# 1Sheet1-IR-Sensor.net
KiCad netlist of a schematic drawn in Altium Designer
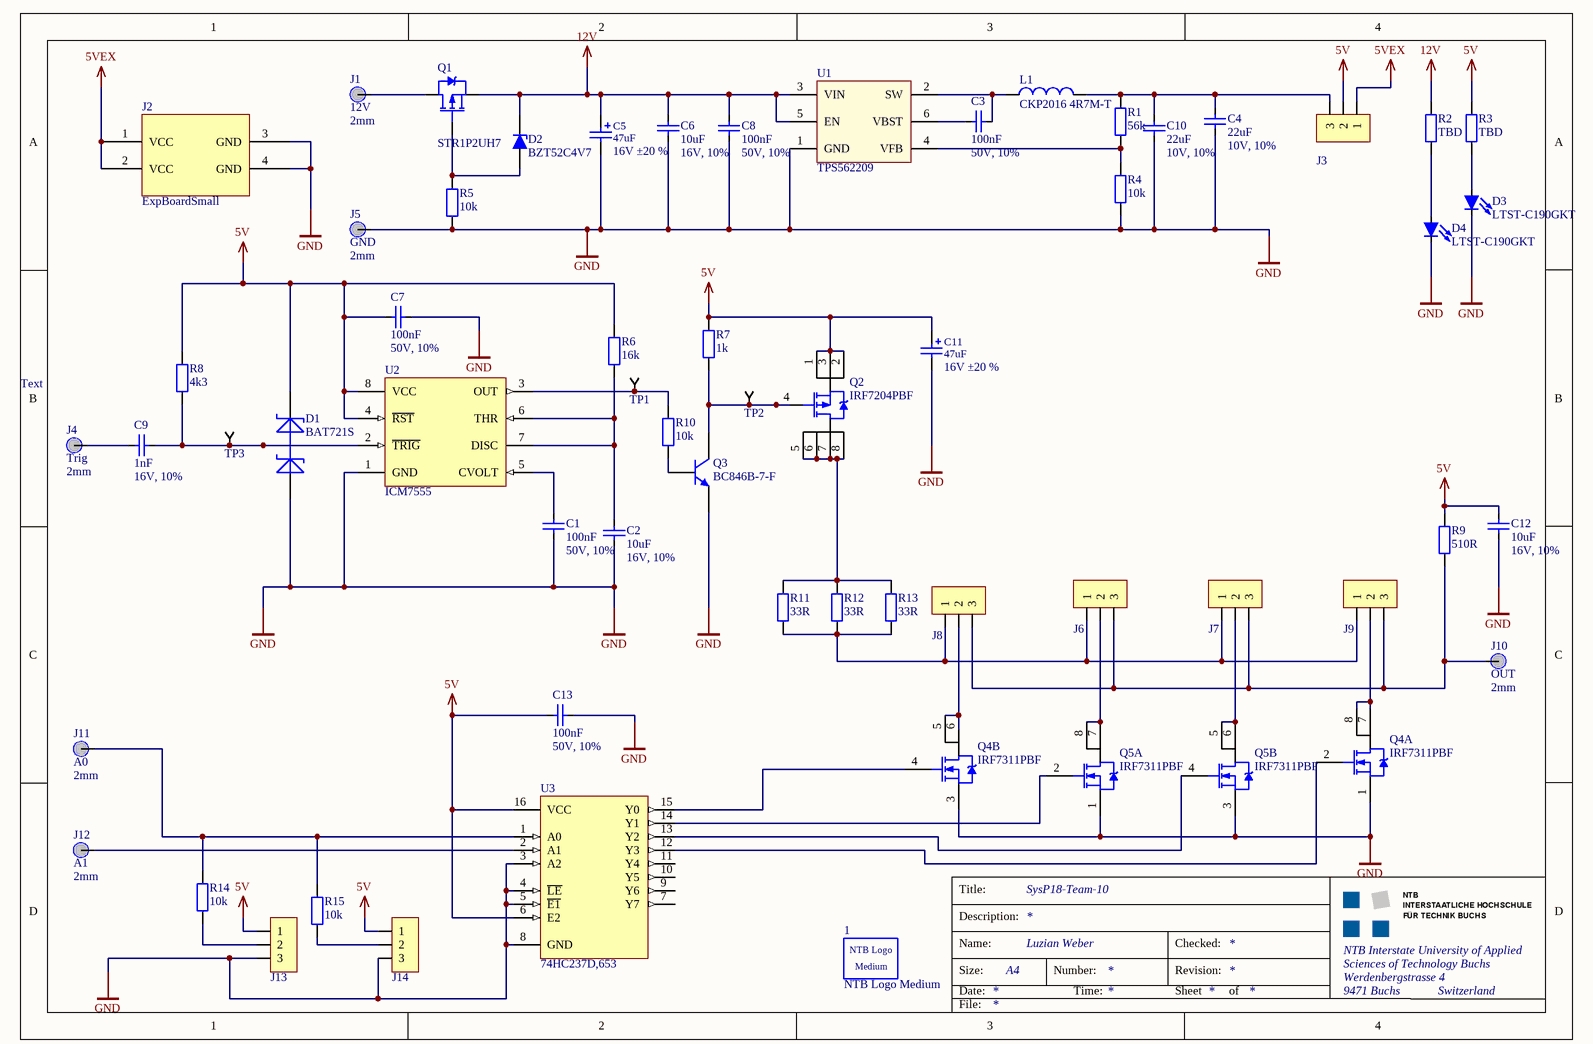
[diagram p0: 1Sheet1-IR-Sensor.SchDoc]

(export (version "E")
  (design (tool "Eeschema 10.0.6"))
  (components
    (comp (ref "1")
      (value "NTB Logo Medium")
      (footprint "NTB Logo Medium Copper")
      (libsource (lib "IR-Sensor") (part "NTB Logo Medium Copper"))
    )
    (comp (ref "C1")
      (value "100nF")
      (footprint "CAP-0805[2012]")
      (description "100n 50V X7R MLCC 0805 (1608 Metric)")
      (fields (field (name "TOLERANCE") "10%") (field (name "VALADDON") "50V, 10%"))
      (libsource (lib "IR-Sensor") (part "MLCC 0805 100n 50V"))
    )
    (comp (ref "C2")
      (value "10uF")
      (footprint "CAP-1206[3216]")
      (description "10u 16V X7R MLCC 1206 (3016 Metric)")
      (fields (field (name "TOLERANCE") "10%") (field (name "VALADDON") "16V, 10%"))
      (libsource (lib "IR-Sensor") (part "MLCC 1206 10u 16V"))
    )
    (comp (ref "C3")
      (value "100nF")
      (footprint "CAP-0805[2012]")
      (description "100n 50V X7R MLCC 0805 (1608 Metric)")
      (fields (field (name "TOLERANCE") "10%") (field (name "VALADDON") "50V, 10%"))
      (libsource (lib "IR-Sensor") (part "MLCC 0805 100n 50V"))
    )
    (comp (ref "C4")
      (value "22uF")
      (footprint "CAP-1206[3216]")
      (description "22u 10V X7R MLCC 1206 (3016 Metric)")
      (fields (field (name "TOLERANCE") "10%") (field (name "VALADDON") "10V, 10%"))
      (libsource (lib "IR-Sensor") (part "MLCC 1206 22u 10V"))
    )
    (comp (ref "C5")
      (value "47uF")
      (footprint "CDE_CAP AVE CODE D_H")
      (description "ELKO, 47uF, 16V, CDE_AVE476M16D16T-F_AVE CODE D")
      (fields
        (field (name "MANUFACTURER") "Cornell Dubilier")
        (field (name "VALUEADDON") "16V ±20 %")
        (field (name "Comment") "AVE476M16D16T-F")
        (field (name "PUBLISHER") "Stefan Ursella, M.Eng")
      )
      (libsource (lib "IR-Sensor") (part "ELKO 47uF 16V"))
    )
    (comp (ref "C6")
      (value "10uF")
      (footprint "CAP-1206[3216]")
      (description "10u 16V X7R MLCC 1206 (3016 Metric)")
      (fields (field (name "TOLERANCE") "10%") (field (name "VALADDON") "16V, 10%"))
      (libsource (lib "IR-Sensor") (part "MLCC 1206 10u 16V"))
    )
    (comp (ref "C7")
      (value "100nF")
      (footprint "CAP-0805[2012]")
      (description "100n 50V X7R MLCC 0805 (1608 Metric)")
      (fields (field (name "TOLERANCE") "10%") (field (name "VALADDON") "50V, 10%"))
      (libsource (lib "IR-Sensor") (part "MLCC 0805 100n 50V"))
    )
    (comp (ref "C8")
      (value "100nF")
      (footprint "CAP-0805[2012]")
      (description "100n 50V X7R MLCC 0805 (1608 Metric)")
      (fields (field (name "TOLERANCE") "10%") (field (name "VALADDON") "50V, 10%"))
      (libsource (lib "IR-Sensor") (part "MLCC 0805 100n 50V"))
    )
    (comp (ref "C9")
      (value "1nF")
      (footprint "CAP-0805[2012]")
      (description "MLCC - SMD/SMT 0805 1000pF 16V C0G 10%")
      (fields
        (field (name "MANUFACTURER") "Vishay")
        (field (name "VALUEADDON") "16V, 10%")
        (field (name "PUBLISHER") "SCLM")
      )
      (libsource (lib "IR-Sensor") (part "MLCC 0805 1n 16V"))
    )
    (comp (ref "C10")
      (value "22uF")
      (footprint "CAP-1206[3216]")
      (description "22u 10V X7R MLCC 1206 (3016 Metric)")
      (fields (field (name "TOLERANCE") "10%") (field (name "VALADDON") "10V, 10%"))
      (libsource (lib "IR-Sensor") (part "MLCC 1206 22u 10V"))
    )
    (comp (ref "C11")
      (value "47uF")
      (footprint "CDE_CAP AVE CODE D_H")
      (description "ELKO, 47uF, 16V, CDE_AVE476M16D16T-F_AVE CODE D")
      (fields
        (field (name "MANUFACTURER") "Cornell Dubilier")
        (field (name "VALUEADDON") "16V ±20 %")
        (field (name "Comment") "AVE476M16D16T-F")
        (field (name "PUBLISHER") "Stefan Ursella, M.Eng")
      )
      (libsource (lib "IR-Sensor") (part "ELKO 47uF 16V"))
    )
    (comp (ref "C12")
      (value "10uF")
      (footprint "CAP-1206[3216]")
      (description "10u 16V X7R MLCC 1206 (3016 Metric)")
      (fields (field (name "TOLERANCE") "10%") (field (name "VALADDON") "16V, 10%"))
      (libsource (lib "IR-Sensor") (part "MLCC 1206 10u 16V"))
    )
    (comp (ref "C13")
      (value "100nF")
      (footprint "CAP-0805[2012]")
      (description "100n 50V X7R MLCC 0805 (1608 Metric)")
      (fields (field (name "TOLERANCE") "10%") (field (name "VALADDON") "50V, 10%"))
      (libsource (lib "IR-Sensor") (part "MLCC 0805 100n 50V"))
    )
    (comp (ref "D1")
      (value "BAT721S")
      (footprint "SOT-23")
      (description "NXP  BAT721S  SCHOTTKY-DIODE, 2FACH")
      (fields (field (name "MANUFACTURER") "NXP") (field (name "PUBLISHER") "SCNP"))
      (libsource (lib "IR-Sensor") (part "BAT721S-SOT23"))
    )
    (comp (ref "D2")
      (value "BZT52C4V7")
      (footprint "SOD-123")
      (description "4.7V Zener-Diode, BZT52C4V7")
      (libsource (lib "IR-Sensor") (part "BZT52C4V7"))
    )
    (comp (ref "D3")
      (value "LTST-C190GKT")
      (footprint "LED 0603 green")
      (description "LED SMD 0603 green 6mcd")
      (libsource (lib "IR-Sensor") (part "LED Green"))
    )
    (comp (ref "D4")
      (value "LTST-C190GKT")
      (footprint "LED 0603 green")
      (description "LED SMD 0603 green 6mcd")
      (libsource (lib "IR-Sensor") (part "LED Green"))
    )
    (comp (ref "J1")
      (value "12V")
      (footprint "Laborbuchse 2mm")
      (description "Laborbuchse")
      (fields (field (name "SIZE") "2mm") (field (name "PUBLISHER") "B.Sc. Ursella"))
      (libsource (lib "") (part "Laborbuchse_1"))
    )
    (comp (ref "J2")
      (value "ExpBoardSmall")
      (footprint "EXPBOARDCON")
      (libsource (lib "IR-Sensor") (part "ExpBoardSmall"))
    )
    (comp (ref "J3")
      (value "3 Pin Header")
      (footprint "3PIN HEADER 2.54MM")
      (description "3 Pin Header 2.54mm")
      (fields (field (name "PUBLISHER") "SCLM"))
      (libsource (lib "") (part "3 Pin Header_1"))
    )
    (comp (ref "J4")
      (value "Trig")
      (footprint "Laborbuchse 2mm")
      (description "Laborbuchse")
      (fields (field (name "SIZE") "2mm") (field (name "PUBLISHER") "B.Sc. Ursella"))
      (libsource (lib "") (part "Laborbuchse_1"))
    )
    (comp (ref "J5")
      (value "GND")
      (footprint "Laborbuchse 2mm")
      (description "Laborbuchse")
      (fields (field (name "SIZE") "2mm") (field (name "PUBLISHER") "B.Sc. Ursella"))
      (libsource (lib "") (part "Laborbuchse_1"))
    )
    (comp (ref "J6")
      (value "3 Pin Header Buchse")
      (footprint "3PIN HEADER SOCKET 2.54MM")
      (description "3 Pin Header 2.54mm Buchse")
      (libsource (lib "IR-Sensor") (part "3 Pin Header Buchse"))
    )
    (comp (ref "J7")
      (value "3 Pin Header Buchse")
      (footprint "3PIN HEADER SOCKET 2.54MM")
      (description "3 Pin Header 2.54mm Buchse")
      (libsource (lib "IR-Sensor") (part "3 Pin Header Buchse"))
    )
    (comp (ref "J8")
      (value "3 Pin Header Buchse")
      (footprint "3PIN HEADER SOCKET 2.54MM")
      (description "3 Pin Header 2.54mm Buchse")
      (libsource (lib "IR-Sensor") (part "3 Pin Header Buchse"))
    )
    (comp (ref "J9")
      (value "3 Pin Header Buchse")
      (footprint "3PIN HEADER SOCKET 2.54MM")
      (description "3 Pin Header 2.54mm Buchse")
      (libsource (lib "IR-Sensor") (part "3 Pin Header Buchse"))
    )
    (comp (ref "J10")
      (value "OUT")
      (footprint "Laborbuchse 2mm")
      (description "Laborbuchse")
      (fields (field (name "SIZE") "2mm") (field (name "PUBLISHER") "B.Sc. Ursella"))
      (libsource (lib "IR-Sensor") (part "Laborbuchse"))
    )
    (comp (ref "J11")
      (value "A0")
      (footprint "Laborbuchse 2mm")
      (description "Laborbuchse")
      (fields (field (name "SIZE") "2mm") (field (name "PUBLISHER") "B.Sc. Ursella"))
      (libsource (lib "") (part "Laborbuchse_1"))
    )
    (comp (ref "J12")
      (value "A1")
      (footprint "Laborbuchse 2mm")
      (description "Laborbuchse")
      (fields (field (name "SIZE") "2mm") (field (name "PUBLISHER") "B.Sc. Ursella"))
      (libsource (lib "") (part "Laborbuchse_1"))
    )
    (comp (ref "J13")
      (value "3 Pin Header")
      (footprint "3PIN HEADER 2.54MM")
      (description "3 Pin Header 2.54mm")
      (fields (field (name "PUBLISHER") "SCLM"))
      (libsource (lib "IR-Sensor") (part "3 Pin Header"))
    )
    (comp (ref "J14")
      (value "3 Pin Header")
      (footprint "3PIN HEADER 2.54MM")
      (description "3 Pin Header 2.54mm")
      (fields (field (name "PUBLISHER") "SCLM"))
      (libsource (lib "IR-Sensor") (part "3 Pin Header"))
    )
    (comp (ref "L1")
      (value "CKP2016 4R7M-T")
      (footprint "IND-0806")
      (description "MULTILAYER CHIP POWER INDUCTORS")
      (libsource (lib "IR-Sensor") (part "L 4.7u"))
    )
    (comp (ref "Q1")
      (value "STR1P2UH7")
      (footprint "SOT-23")
      (description "Low Power P-Kanal Mosfet")
      (fields (field (name "MANUFACTURER") "ST Microelectronics"))
      (libsource (lib "IR-Sensor") (part "STR1P2UH7"))
    )
    (comp (ref "Q2")
      (value "IRF7204PBF")
      (footprint "SOIC-8")
      (description "High Power P-Kanal Mosfet")
      (fields
        (field (name "MANUFACTURER") "International Rectifiers")
        (field (name "PUBLISHER") "Altium Limited")
      )
      (libsource (lib "IR-Sensor") (part "IRF7204"))
    )
    (comp (ref "Q3")
      (value "BC846B-7-F")
      (footprint "SOT-23")
      (description "NPN General-purpose Transistor")
      (fields (field (name "MANUFACTURER") "DIODES INC") (field (name "PUBLISHER") "Altium Limited"))
      (libsource (lib "IR-Sensor") (part "BC846B-SOT23"))
    )
    (comp (ref "Q4")
      (value "IRF7311PBF")
      (footprint "SOIC-8")
      (description "Dual N-Kanal Mosfet")
      (fields
        (field (name "MANUFACTURER") "International Rectifier")
        (field (name "PUBLISHER") "Altium Limited")
      )
      (libsource (lib "IR-Sensor") (part "IRF7311"))
    )
    (comp (ref "Q5")
      (value "IRF7311PBF")
      (footprint "SOIC-8")
      (description "Dual N-Kanal Mosfet")
      (fields
        (field (name "MANUFACTURER") "International Rectifier")
        (field (name "PUBLISHER") "Altium Limited")
      )
      (libsource (lib "IR-Sensor") (part "IRF7311"))
    )
    (comp (ref "R1")
      (value "56k")
      (footprint "RES-0603[1608]")
      (description "0603 (1608 Metric) 1/10 W 10K 1 Thick Film Chip Resistor")
      (fields (field (name "POWER") "1/10 W") (field (name "TOLERANCE") "1%"))
      (libsource (lib "IR-Sensor") (part "RES 0603"))
    )
    (comp (ref "R2")
      (value "TBD")
      (footprint "RES-0603[1608]")
      (description "0603 (1608 Metric) 1/10 W 10K 1 Thick Film Chip Resistor")
      (fields (field (name "POWER") "1/10 W") (field (name "TOLERANCE") "1%"))
      (libsource (lib "IR-Sensor") (part "RES 0603"))
    )
    (comp (ref "R3")
      (value "TBD")
      (footprint "RES-0603[1608]")
      (description "0603 (1608 Metric) 1/10 W 10K 1 Thick Film Chip Resistor")
      (fields (field (name "POWER") "1/10 W") (field (name "TOLERANCE") "1%"))
      (libsource (lib "IR-Sensor") (part "RES 0603"))
    )
    (comp (ref "R4")
      (value "10k")
      (footprint "RES-0603[1608]")
      (description "0603 (1608 Metric) 1/10 W 10K 1 Thick Film Chip Resistor")
      (fields (field (name "POWER") "1/10 W") (field (name "TOLERANCE") "1%"))
      (libsource (lib "IR-Sensor") (part "RES 0603"))
    )
    (comp (ref "R5")
      (value "10k")
      (footprint "RES-0603[1608]")
      (description "0603 (1608 Metric) 1/10 W 10K 1 Thick Film Chip Resistor")
      (fields (field (name "POWER") "1/10 W") (field (name "TOLERANCE") "1%"))
      (libsource (lib "IR-Sensor") (part "RES 0603"))
    )
    (comp (ref "R6")
      (value "16k")
      (footprint "RES-0805[2012]")
      (description "0805 (2013 Metric) 1/10 W 10K 1 Thick Film Chip Resistor")
      (fields (field (name "POWER") "1/10 W") (field (name "TOLERANCE") "1%"))
      (libsource (lib "IR-Sensor") (part "RES 0805"))
    )
    (comp (ref "R7")
      (value "1k")
      (footprint "RES-0805[2012]")
      (description "0805 (2013 Metric) 1/10 W 10K 1 Thick Film Chip Resistor")
      (fields (field (name "POWER") "1/10 W") (field (name "TOLERANCE") "1%"))
      (libsource (lib "IR-Sensor") (part "RES 0805"))
    )
    (comp (ref "R8")
      (value "4k3")
      (footprint "RES-0805[2012]")
      (description "0805 (2013 Metric) 1/10 W 10K 1 Thick Film Chip Resistor")
      (fields (field (name "POWER") "1/10 W") (field (name "TOLERANCE") "1%"))
      (libsource (lib "IR-Sensor") (part "RES 0805"))
    )
    (comp (ref "R9")
      (value "510R")
      (footprint "RES-0805[2012]")
      (description "0805 (2013 Metric) 1/10 W 10K 1 Thick Film Chip Resistor")
      (fields (field (name "POWER") "1/10 W") (field (name "TOLERANCE") "1%"))
      (libsource (lib "IR-Sensor") (part "RES 0805"))
    )
    (comp (ref "R10")
      (value "10k")
      (footprint "RES-0805[2012]")
      (description "0805 (2013 Metric) 1/10 W 10K 1 Thick Film Chip Resistor")
      (fields (field (name "POWER") "1/10 W") (field (name "TOLERANCE") "1%"))
      (libsource (lib "IR-Sensor") (part "RES 0805"))
    )
    (comp (ref "R11")
      (value "33R")
      (footprint "RES-0805[2012]")
      (description "0805 (2013 Metric) 1/10 W 10K 1 Thick Film Chip Resistor")
      (fields (field (name "POWER") "1/10 W") (field (name "TOLERANCE") "1%"))
      (libsource (lib "IR-Sensor") (part "RES 0805"))
    )
    (comp (ref "R12")
      (value "33R")
      (footprint "RES-0805[2012]")
      (description "0805 (2013 Metric) 1/10 W 10K 1 Thick Film Chip Resistor")
      (fields (field (name "POWER") "1/10 W") (field (name "TOLERANCE") "1%"))
      (libsource (lib "IR-Sensor") (part "RES 0805"))
    )
    (comp (ref "R13")
      (value "33R")
      (footprint "RES-0805[2012]")
      (description "0805 (2013 Metric) 1/10 W 10K 1 Thick Film Chip Resistor")
      (fields (field (name "POWER") "1/10 W") (field (name "TOLERANCE") "1%"))
      (libsource (lib "IR-Sensor") (part "RES 0805"))
    )
    (comp (ref "R14")
      (value "10k")
      (footprint "RES-0805[2012]")
      (description "0805 (2013 Metric) 1/10 W 10K 1 Thick Film Chip Resistor")
      (fields (field (name "POWER") "1/10 W") (field (name "TOLERANCE") "1%"))
      (libsource (lib "IR-Sensor") (part "RES 0805"))
    )
    (comp (ref "R15")
      (value "10k")
      (footprint "RES-0805[2012]")
      (description "0805 (2013 Metric) 1/10 W 10K 1 Thick Film Chip Resistor")
      (fields (field (name "POWER") "1/10 W") (field (name "TOLERANCE") "1%"))
      (libsource (lib "IR-Sensor") (part "RES 0805"))
    )
    (comp (ref "TP1")
      (value "Testpoint SMD 1206")
      (footprint "TP-SMD-1206")
      (description "Testpoint xSmall")
      (libsource (lib "IR-Sensor") (part "Testpoint SMD 1206"))
    )
    (comp (ref "TP2")
      (value "Testpunkt THT 1mm")
      (footprint "TP-THT-1.1mm")
      (fields (field (name "MANUFACTURER") "Keystone Electronics") (field (name "PUBLISHER") "B.Sc. Ursella"))
      (libsource (lib "IR-Sensor") (part "Testpunkt THT 1mm"))
    )
    (comp (ref "TP3")
      (value "Testpunkt THT 1mm")
      (footprint "TP-THT-1.1mm")
      (fields (field (name "MANUFACTURER") "Keystone Electronics") (field (name "PUBLISHER") "B.Sc. Ursella"))
      (libsource (lib "IR-Sensor") (part "Testpunkt THT 1mm"))
    )
    (comp (ref "U1")
      (value "TPS562209")
      (footprint "SOT-23-6")
      (description "3-A Synchronous Step-Down Voltage Regulator")
      (libsource (lib "IR-Sensor") (part "TPS562209-SOT23-6"))
    )
    (comp (ref "U2")
      (value "ICM7555")
      (footprint "SOIC-8")
      (description "General purpose CMOS timer")
      (fields
        (field (name "MANUFACTURER") "National Semiconductor")
        (field (name "PUBLISHER") "Altium Hobart Technology Centre")
      )
      (libsource (lib "IR-Sensor") (part "ICM7555-SOIC8"))
    )
    (comp (ref "U3")
      (value "74HC237D,653")
      (footprint "SOIC-16")
      (description "3-to-8 line decoder, demultiplexer, NXP, SO16")
      (fields (field (name "MANUFACTURER") "NXP") (field (name "PUBLISHER") "SCLM"))
      (libsource (lib "IR-Sensor") (part "74HC237D-SOIC16"))
    )
  )
  (nets
    (net (code "1") (name "5V") (class "Default")
      (node (ref "C11") (pin "1") (pinfunction "Pos_1") (pintype "passive"))
      (node (ref "C12") (pin "1") (pinfunction "Pos_1") (pintype "passive"))
      (node (ref "C13") (pin "1") (pinfunction "Pos_1") (pintype "passive"))
      (node (ref "C7") (pin "1") (pinfunction "Pos_1") (pintype "passive"))
      (node (ref "D1") (pin "2") (pinfunction "cathode2_2") (pintype "passive"))
      (node (ref "J13") (pin "1") (pinfunction "1_1") (pintype "passive"))
      (node (ref "J14") (pin "1") (pinfunction "1_1") (pintype "passive"))
      (node (ref "J3") (pin "2") (pinfunction "2_2") (pintype "passive"))
      (node (ref "Q2") (pin "1") (pinfunction "S_1") (pintype "passive"))
      (node (ref "Q2") (pin "2") (pinfunction "S_2") (pintype "passive"))
      (node (ref "Q2") (pin "3") (pinfunction "S_3") (pintype "passive"))
      (node (ref "R3") (pin "2") (pinfunction "2_2") (pintype "passive"))
      (node (ref "R6") (pin "2") (pinfunction "2_2") (pintype "passive"))
      (node (ref "R7") (pin "2") (pinfunction "2_2") (pintype "passive"))
      (node (ref "R8") (pin "2") (pinfunction "2_2") (pintype "passive"))
      (node (ref "R9") (pin "2") (pinfunction "2_2") (pintype "passive"))
      (node (ref "U2") (pin "4") (pinfunction "~{RST}_4") (pintype "input"))
      (node (ref "U2") (pin "8") (pinfunction "VCC_8") (pintype "power_in"))
      (node (ref "U3") (pin "16") (pinfunction "VCC_16") (pintype "power_in"))
      (node (ref "U3") (pin "6") (pinfunction "E2_6") (pintype "input"))
    )
    (net (code "2") (name "5VEX") (class "Default")
      (node (ref "J2") (pin "1") (pinfunction "VCC_1") (pintype "passive"))
      (node (ref "J2") (pin "2") (pinfunction "VCC_2") (pintype "passive"))
      (node (ref "J3") (pin "1") (pinfunction "1_1") (pintype "passive"))
    )
    (net (code "3") (name "12V") (class "Default")
      (node (ref "C5") (pin "1") (pinfunction "Pos_1") (pintype "passive"))
      (node (ref "C6") (pin "1") (pinfunction "Pos_1") (pintype "passive"))
      (node (ref "C8") (pin "1") (pinfunction "Pos_1") (pintype "passive"))
      (node (ref "D2") (pin "1") (pinfunction "K_1") (pintype "passive"))
      (node (ref "Q1") (pin "2") (pinfunction "S_2") (pintype "passive"))
      (node (ref "R2") (pin "2") (pinfunction "2_2") (pintype "passive"))
      (node (ref "U1") (pin "3") (pinfunction "VIN_3") (pintype "passive"))
      (node (ref "U1") (pin "5") (pinfunction "EN_5") (pintype "passive"))
    )
    (net (code "4") (name "GND") (class "Default")
      (node (ref "C1") (pin "2") (pinfunction "Neg_2") (pintype "passive"))
      (node (ref "C10") (pin "2") (pinfunction "Neg_2") (pintype "passive"))
      (node (ref "C11") (pin "2") (pinfunction "Neg_2") (pintype "passive"))
      (node (ref "C12") (pin "2") (pinfunction "Neg_2") (pintype "passive"))
      (node (ref "C13") (pin "2") (pinfunction "Neg_2") (pintype "passive"))
      (node (ref "C2") (pin "2") (pinfunction "Neg_2") (pintype "passive"))
      (node (ref "C4") (pin "2") (pinfunction "Neg_2") (pintype "passive"))
      (node (ref "C5") (pin "2") (pinfunction "Neg_2") (pintype "passive"))
      (node (ref "C6") (pin "2") (pinfunction "Neg_2") (pintype "passive"))
      (node (ref "C7") (pin "2") (pinfunction "Neg_2") (pintype "passive"))
      (node (ref "C8") (pin "2") (pinfunction "Neg_2") (pintype "passive"))
      (node (ref "D1") (pin "1") (pinfunction "Anode1_1") (pintype "passive"))
      (node (ref "D3") (pin "1") (pinfunction "K_1") (pintype "passive"))
      (node (ref "D4") (pin "1") (pinfunction "K_1") (pintype "passive"))
      (node (ref "J13") (pin "3") (pinfunction "3_3") (pintype "passive"))
      (node (ref "J14") (pin "3") (pinfunction "3_3") (pintype "passive"))
      (node (ref "J2") (pin "3") (pinfunction "GND_3") (pintype "passive"))
      (node (ref "J2") (pin "4") (pinfunction "GND_4") (pintype "passive"))
      (node (ref "J5") (pin "1") (pinfunction "1_1") (pintype "passive"))
      (node (ref "Q3") (pin "2") (pinfunction "E_2") (pintype "passive"))
      (node (ref "Q4") (pin "1") (pinfunction "S_1") (pintype "passive"))
      (node (ref "Q4") (pin "3") (pinfunction "S_3") (pintype "passive"))
      (node (ref "Q5") (pin "1") (pinfunction "S_1") (pintype "passive"))
      (node (ref "Q5") (pin "3") (pinfunction "S_3") (pintype "passive"))
      (node (ref "R4") (pin "1") (pinfunction "1_1") (pintype "passive"))
      (node (ref "R5") (pin "1") (pinfunction "1_1") (pintype "passive"))
      (node (ref "U1") (pin "1") (pinfunction "GND_1") (pintype "passive"))
      (node (ref "U2") (pin "1") (pinfunction "GND_1") (pintype "power_in"))
      (node (ref "U3") (pin "3") (pinfunction "A2_3") (pintype "input"))
      (node (ref "U3") (pin "4") (pinfunction "LE_4") (pintype "input"))
      (node (ref "U3") (pin "5") (pinfunction "E1_5") (pintype "input"))
      (node (ref "U3") (pin "8") (pinfunction "GND_8") (pintype "power_in"))
    )
    (net (code "5") (name "Net-(C1-Pos)") (class "Default")
      (node (ref "C1") (pin "1") (pinfunction "Pos_1") (pintype "passive"))
      (node (ref "U2") (pin "5") (pinfunction "CVOLT_5") (pintype "input"))
    )
    (net (code "6") (name "Net-(C2-Pos)") (class "Default")
      (node (ref "C2") (pin "1") (pinfunction "Pos_1") (pintype "passive"))
      (node (ref "R6") (pin "1") (pinfunction "1_1") (pintype "passive"))
      (node (ref "U2") (pin "6") (pinfunction "THR_6") (pintype "input"))
      (node (ref "U2") (pin "7") (pinfunction "DISC_7") (pintype "open_collector"))
    )
    (net (code "7") (name "Net-(C3-Neg)") (class "Default")
      (node (ref "C3") (pin "2") (pinfunction "Neg_2") (pintype "passive"))
      (node (ref "L1") (pin "1") (pinfunction "1_1") (pintype "passive"))
      (node (ref "U1") (pin "2") (pinfunction "SW_2") (pintype "passive"))
    )
    (net (code "8") (name "Net-(C3-Pos)") (class "Default")
      (node (ref "C3") (pin "1") (pinfunction "Pos_1") (pintype "passive"))
      (node (ref "U1") (pin "6") (pinfunction "VBST_6") (pintype "passive"))
    )
    (net (code "9") (name "Net-(C9-Neg)") (class "Default")
      (node (ref "C9") (pin "2") (pinfunction "Neg_2") (pintype "passive"))
      (node (ref "D1") (pin "3") (pinfunction "Cathode1,_anode2_3") (pintype "passive"))
      (node (ref "R8") (pin "1") (pinfunction "1_1") (pintype "passive"))
      (node (ref "TP3") (pin "1") (pinfunction "0_1") (pintype "passive"))
      (node (ref "U2") (pin "2") (pinfunction "TRIG_2") (pintype "input"))
    )
    (net (code "10") (name "Net-(C9-Pos)") (class "Default")
      (node (ref "C9") (pin "1") (pinfunction "Pos_1") (pintype "passive"))
      (node (ref "J4") (pin "1") (pinfunction "1_1") (pintype "passive"))
    )
    (net (code "11") (name "Net-(C10-Pos)") (class "Default")
      (node (ref "C10") (pin "1") (pinfunction "Pos_1") (pintype "passive"))
      (node (ref "C4") (pin "1") (pinfunction "Pos_1") (pintype "passive"))
      (node (ref "J3") (pin "3") (pinfunction "3_3") (pintype "passive"))
      (node (ref "L1") (pin "2") (pinfunction "2_2") (pintype "passive"))
      (node (ref "R1") (pin "2") (pinfunction "2_2") (pintype "passive"))
    )
    (net (code "12") (name "Net-(D2-A)") (class "Default")
      (node (ref "D2") (pin "2") (pinfunction "A_2") (pintype "passive"))
      (node (ref "Q1") (pin "1") (pinfunction "G_1") (pintype "passive"))
      (node (ref "R5") (pin "2") (pinfunction "2_2") (pintype "passive"))
    )
    (net (code "13") (name "Net-(D3-A)") (class "Default")
      (node (ref "D3") (pin "2") (pinfunction "A_2") (pintype "passive"))
      (node (ref "R3") (pin "1") (pinfunction "1_1") (pintype "passive"))
    )
    (net (code "14") (name "Net-(D4-A)") (class "Default")
      (node (ref "D4") (pin "2") (pinfunction "A_2") (pintype "passive"))
      (node (ref "R2") (pin "1") (pinfunction "1_1") (pintype "passive"))
    )
    (net (code "15") (name "Net-(J6-Pad1)") (class "Default")
      (node (ref "J6") (pin "1") (pinfunction "1_1") (pintype "passive"))
      (node (ref "J7") (pin "1") (pinfunction "1_1") (pintype "passive"))
      (node (ref "J8") (pin "1") (pinfunction "1_1") (pintype "passive"))
      (node (ref "J9") (pin "1") (pinfunction "1_1") (pintype "passive"))
      (node (ref "R11") (pin "1") (pinfunction "1_1") (pintype "passive"))
      (node (ref "R12") (pin "1") (pinfunction "1_1") (pintype "passive"))
      (node (ref "R13") (pin "1") (pinfunction "1_1") (pintype "passive"))
    )
    (net (code "16") (name "Net-(J6-Pad2)") (class "Default")
      (node (ref "J6") (pin "2") (pinfunction "2_2") (pintype "passive"))
      (node (ref "Q5") (pin "7") (pinfunction "D_7") (pintype "passive"))
      (node (ref "Q5") (pin "8") (pinfunction "D_8") (pintype "passive"))
    )
    (net (code "17") (name "Net-(J7-Pad2)") (class "Default")
      (node (ref "J7") (pin "2") (pinfunction "2_2") (pintype "passive"))
      (node (ref "Q5") (pin "5") (pinfunction "D_5") (pintype "passive"))
      (node (ref "Q5") (pin "6") (pinfunction "D_6") (pintype "passive"))
    )
    (net (code "18") (name "Net-(J8-Pad2)") (class "Default")
      (node (ref "J8") (pin "2") (pinfunction "2_2") (pintype "passive"))
      (node (ref "Q4") (pin "5") (pinfunction "D_5") (pintype "passive"))
      (node (ref "Q4") (pin "6") (pinfunction "D_6") (pintype "passive"))
    )
    (net (code "19") (name "Net-(J9-Pad2)") (class "Default")
      (node (ref "J9") (pin "2") (pinfunction "2_2") (pintype "passive"))
      (node (ref "Q4") (pin "7") (pinfunction "D_7") (pintype "passive"))
      (node (ref "Q4") (pin "8") (pinfunction "D_8") (pintype "passive"))
    )
    (net (code "20") (name "Net-(J10-Pad1)") (class "Default")
      (node (ref "J10") (pin "1") (pinfunction "1_1") (pintype "passive"))
      (node (ref "J6") (pin "3") (pinfunction "3_3") (pintype "passive"))
      (node (ref "J7") (pin "3") (pinfunction "3_3") (pintype "passive"))
      (node (ref "J8") (pin "3") (pinfunction "3_3") (pintype "passive"))
      (node (ref "J9") (pin "3") (pinfunction "3_3") (pintype "passive"))
      (node (ref "R9") (pin "1") (pinfunction "1_1") (pintype "passive"))
    )
    (net (code "21") (name "Net-(J13-Pad2)") (class "Default")
      (node (ref "J13") (pin "2") (pinfunction "2_2") (pintype "passive"))
      (node (ref "R14") (pin "1") (pinfunction "1_1") (pintype "passive"))
    )
    (net (code "22") (name "Net-(J14-Pad2)") (class "Default")
      (node (ref "J14") (pin "2") (pinfunction "2_2") (pintype "passive"))
      (node (ref "R15") (pin "1") (pinfunction "1_1") (pintype "passive"))
    )
    (net (code "23") (name "Net-(Q1-D)") (class "Default")
      (node (ref "J1") (pin "1") (pinfunction "1_1") (pintype "passive"))
      (node (ref "Q1") (pin "3") (pinfunction "D_3") (pintype "passive"))
    )
    (net (code "24") (name "Net-(Q2-D-Pad5)") (class "Default")
      (node (ref "Q2") (pin "5") (pinfunction "D_5") (pintype "passive"))
      (node (ref "Q2") (pin "6") (pinfunction "D_6") (pintype "passive"))
      (node (ref "Q2") (pin "7") (pinfunction "D_7") (pintype "passive"))
      (node (ref "Q2") (pin "8") (pinfunction "D_8") (pintype "passive"))
      (node (ref "R11") (pin "2") (pinfunction "2_2") (pintype "passive"))
      (node (ref "R12") (pin "2") (pinfunction "2_2") (pintype "passive"))
      (node (ref "R13") (pin "2") (pinfunction "2_2") (pintype "passive"))
    )
    (net (code "25") (name "Net-(Q2-G)") (class "Default")
      (node (ref "Q2") (pin "4") (pinfunction "G_4") (pintype "passive"))
      (node (ref "Q3") (pin "3") (pinfunction "C_3") (pintype "passive"))
      (node (ref "R7") (pin "1") (pinfunction "1_1") (pintype "passive"))
      (node (ref "TP2") (pin "1") (pinfunction "0_1") (pintype "passive"))
    )
    (net (code "26") (name "Net-(Q3-B)") (class "Default")
      (node (ref "Q3") (pin "1") (pinfunction "B_1") (pintype "passive"))
      (node (ref "R10") (pin "1") (pinfunction "1_1") (pintype "passive"))
    )
    (net (code "27") (name "Net-(Q4A-G)") (class "Default")
      (node (ref "Q4") (pin "2") (pinfunction "G_2") (pintype "passive"))
      (node (ref "U3") (pin "12") (pinfunction "Y3_12") (pintype "output"))
    )
    (net (code "28") (name "Net-(Q4B-G)") (class "Default")
      (node (ref "Q4") (pin "4") (pinfunction "G_4") (pintype "passive"))
      (node (ref "U3") (pin "15") (pinfunction "Y0_15") (pintype "output"))
    )
    (net (code "29") (name "Net-(Q5A-G)") (class "Default")
      (node (ref "Q5") (pin "2") (pinfunction "G_2") (pintype "passive"))
      (node (ref "U3") (pin "14") (pinfunction "Y1_14") (pintype "output"))
    )
    (net (code "30") (name "Net-(Q5B-G)") (class "Default")
      (node (ref "Q5") (pin "4") (pinfunction "G_4") (pintype "passive"))
      (node (ref "U3") (pin "13") (pinfunction "Y2_13") (pintype "output"))
    )
    (net (code "31") (name "Net-(TP1-0)") (class "Default")
      (node (ref "R10") (pin "2") (pinfunction "2_2") (pintype "passive"))
      (node (ref "TP1") (pin "1") (pinfunction "0_1") (pintype "passive"))
      (node (ref "U2") (pin "3") (pinfunction "OUT_3") (pintype "output"))
    )
    (net (code "32") (name "Net-(U1-VFB)") (class "Default")
      (node (ref "R1") (pin "1") (pinfunction "1_1") (pintype "passive"))
      (node (ref "R4") (pin "2") (pinfunction "2_2") (pintype "passive"))
      (node (ref "U1") (pin "4") (pinfunction "VFB_4") (pintype "passive"))
    )
    (net (code "33") (name "Net-(U3-A0)") (class "Default")
      (node (ref "J11") (pin "1") (pinfunction "1_1") (pintype "passive"))
      (node (ref "R14") (pin "2") (pinfunction "2_2") (pintype "passive"))
      (node (ref "R15") (pin "2") (pinfunction "2_2") (pintype "passive"))
      (node (ref "U3") (pin "1") (pinfunction "A0_1") (pintype "input"))
    )
    (net (code "34") (name "Net-(U3-A1)") (class "Default")
      (node (ref "J12") (pin "1") (pinfunction "1_1") (pintype "passive"))
      (node (ref "U3") (pin "2") (pinfunction "A1_2") (pintype "input"))
    )
    (net (code "35") (name "unconnected-(U3-Y4-Pad11)") (class "Default")
      (node (ref "U3") (pin "11") (pinfunction "Y4_11") (pintype "output"))
    )
    (net (code "36") (name "unconnected-(U3-Y5-Pad10)") (class "Default")
      (node (ref "U3") (pin "10") (pinfunction "Y5_10") (pintype "output"))
    )
    (net (code "37") (name "unconnected-(U3-Y6-Pad9)") (class "Default")
      (node (ref "U3") (pin "9") (pinfunction "Y6_9") (pintype "output"))
    )
    (net (code "38") (name "unconnected-(U3-Y7-Pad7)") (class "Default")
      (node (ref "U3") (pin "7") (pinfunction "Y7_7") (pintype "output"))
    )
  )
)
